# ESP32.net
KiCad netlist of a schematic drawn in Altium Designer
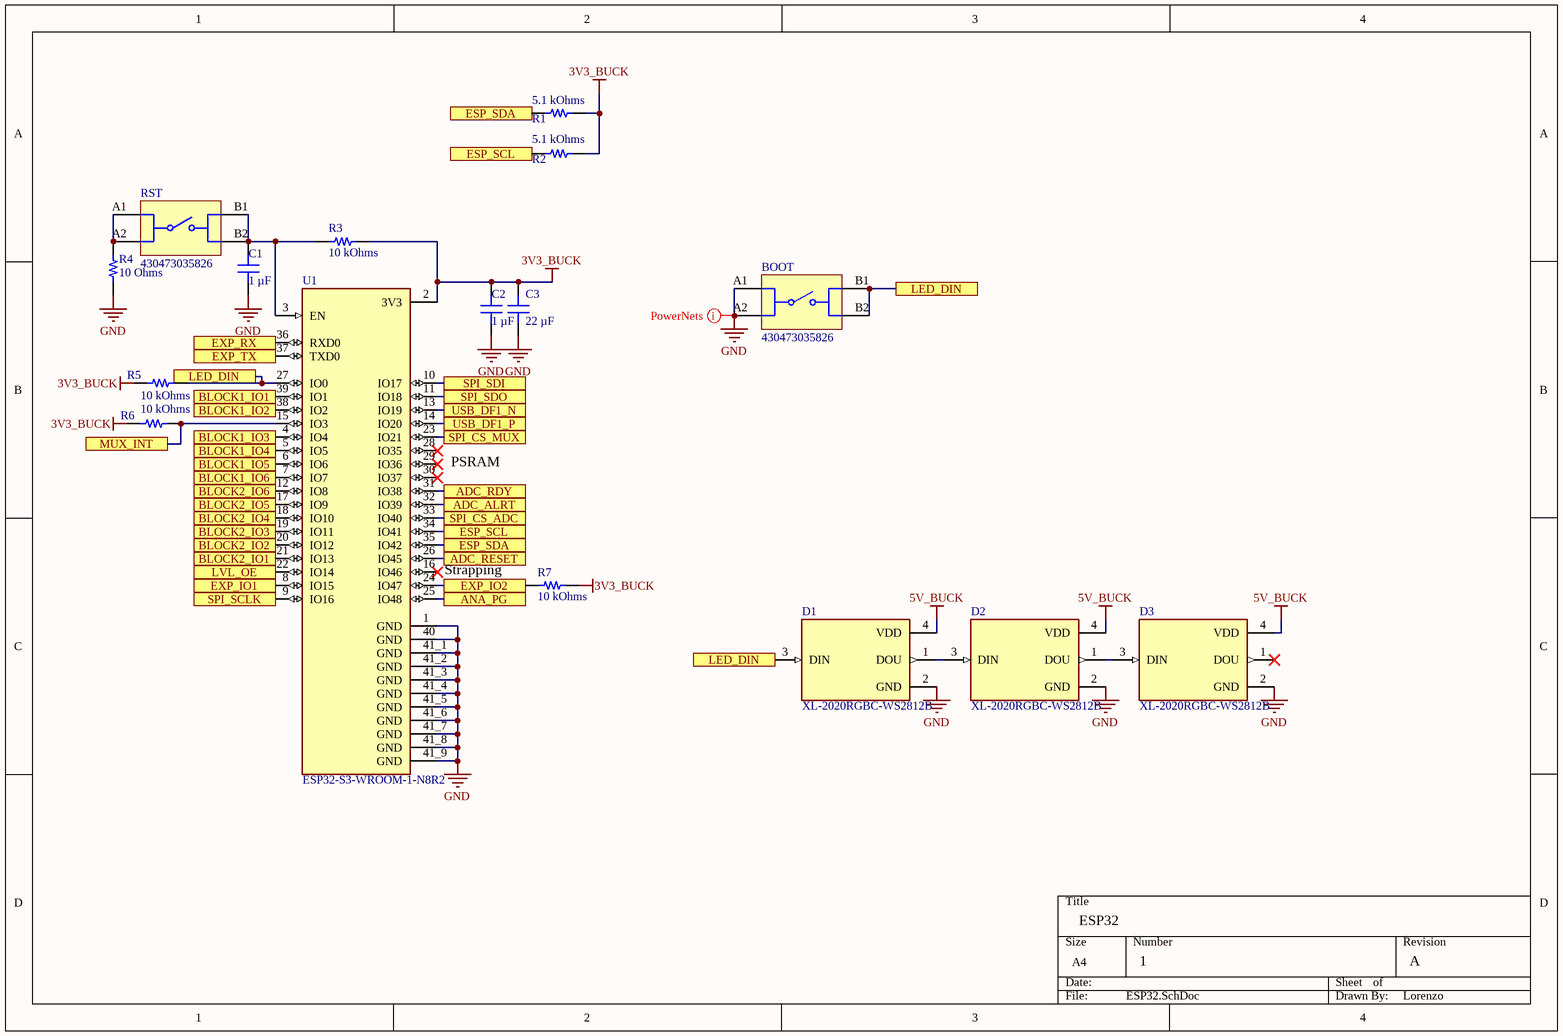
[diagram p0: ESP32.SchDoc]

(export (version "E")
  (design (tool "Eeschema 10.0.6"))
  (components
    (comp (ref "BOOT")
      (value "430473035826")
      (footprint "430473035826")
      (description "Switch Tactile Spst-no 0.05A 12V")
      (libsource (lib "Altium Content Vault") (part "SPST-NO_4P"))
    )
    (comp (ref "C1")
      (value "1 µF")
      (footprint "CAP 0603_1608")
      (description "CAP CER 1UF 50V X5R 0603")
      (fields
        (field (name "PART NUMBER") "C1608X5R1H105K080AB")
        (field (name "MANUFACTURER") "TDK Corporation")
      )
      (libsource (lib "Altium Database Library V2 Local") (part "Capacitor"))
    )
    (comp (ref "C2")
      (value "1 µF")
      (footprint "CAP 0603_1608")
      (description "CAP CER 1UF 50V X5R 0603")
      (fields
        (field (name "PART NUMBER") "C1608X5R1H105K080AB")
        (field (name "MANUFACTURER") "TDK Corporation")
      )
      (libsource (lib "Altium Database Library V2 Local") (part "Capacitor"))
    )
    (comp (ref "C3")
      (value "22 µF")
      (footprint "CAP 0603_1608")
      (description "CAP CER 22UF 6.3V X6S 0603")
      (fields (field (name "PART NUMBER") "CC0603MRX6S5BB226") (field (name "MANUFACTURER") "Yageo"))
      (libsource (lib "Altium Database Library V2 Local") (part "Capacitor"))
    )
    (comp (ref "D1")
      (value "XL-2020RGBC-WS2812B")
      (footprint "LED_XL-2020RGBC-WS2812B")
      (description "2020 RGB LED(BUILT-IN IC)")
      (fields (field (name "MF") "XINGLIGHT"))
      (libsource (lib "Lib") (part "XL-2020RGBC-WS2812B"))
    )
    (comp (ref "D2")
      (value "XL-2020RGBC-WS2812B")
      (footprint "LED_XL-2020RGBC-WS2812B")
      (description "2020 RGB LED(BUILT-IN IC)")
      (fields (field (name "MF") "XINGLIGHT"))
      (libsource (lib "Lib") (part "XL-2020RGBC-WS2812B"))
    )
    (comp (ref "D3")
      (value "XL-2020RGBC-WS2812B")
      (footprint "LED_XL-2020RGBC-WS2812B")
      (description "2020 RGB LED(BUILT-IN IC)")
      (fields (field (name "MF") "XINGLIGHT"))
      (libsource (lib "Lib") (part "XL-2020RGBC-WS2812B"))
    )
    (comp (ref "R1")
      (value "5.1 kOhms")
      (footprint "RES 0603_1608")
      (description "RES 5.1K OHM 1% 1/10W 0603")
      (fields
        (field (name "PART NUMBER") "RMCF0603FT5K10")
        (field (name "MANUFACTURER") "Stackpole Electronics Inc")
      )
      (libsource (lib "Altium Database Library V2 Local") (part "Resistor"))
    )
    (comp (ref "R2")
      (value "5.1 kOhms")
      (footprint "RES 0603_1608")
      (description "RES 5.1K OHM 1% 1/10W 0603")
      (fields
        (field (name "PART NUMBER") "RMCF0603FT5K10")
        (field (name "MANUFACTURER") "Stackpole Electronics Inc")
      )
      (libsource (lib "Altium Database Library V2 Local") (part "Resistor"))
    )
    (comp (ref "R3")
      (value "10 kOhms")
      (footprint "RES 0603_1608")
      (description "RES 10K OHM 1% 1/5W 0603")
      (fields
        (field (name "PART NUMBER") "SG73S1JTTD1002F")
        (field (name "MANUFACTURER") "KOA Speer Electronics, Inc.")
      )
      (libsource (lib "Altium Database Library V2 Local") (part "Resistor"))
    )
    (comp (ref "R4")
      (value "10 Ohms")
      (footprint "RES 0603_1608")
      (description "RES SMD 10 OHM 1% 1/4W 0603")
      (fields (field (name "PART NUMBER") "ESR03EZPF10R0") (field (name "MANUFACTURER") "Rohm Semiconductor"))
      (libsource (lib "Altium Database Library V2 Local") (part "Resistor"))
    )
    (comp (ref "R5")
      (value "10 kOhms")
      (footprint "RES 0603_1608")
      (description "RES 10K OHM 1% 1/5W 0603")
      (fields
        (field (name "PART NUMBER") "SG73S1JTTD1002F")
        (field (name "MANUFACTURER") "KOA Speer Electronics, Inc.")
      )
      (libsource (lib "Altium Database Library V2 Local") (part "Resistor"))
    )
    (comp (ref "R6")
      (value "10 kOhms")
      (footprint "RES 0603_1608")
      (description "RES 10K OHM 1% 1/5W 0603")
      (fields
        (field (name "PART NUMBER") "SG73S1JTTD1002F")
        (field (name "MANUFACTURER") "KOA Speer Electronics, Inc.")
      )
      (libsource (lib "Altium Database Library V2 Local") (part "Resistor"))
    )
    (comp (ref "R7")
      (value "10 kOhms")
      (footprint "RES 0603_1608")
      (description "RES 10K OHM 1% 1/5W 0603")
      (fields
        (field (name "PART NUMBER") "SG73S1JTTD1002F")
        (field (name "MANUFACTURER") "KOA Speer Electronics, Inc.")
      )
      (libsource (lib "Altium Database Library V2 Local") (part "Resistor"))
    )
    (comp (ref "RST")
      (value "430473035826")
      (footprint "430473035826")
      (description "Switch Tactile Spst-no 0.05A 12V")
      (libsource (lib "Altium Content Vault") (part "SPST-NO_4P"))
    )
    (comp (ref "U1")
      (value "ESP32-S3-WROOM-1-N8R2")
      (footprint "XCVR_ESP32-S3-WROOM-1-N8R2")
      (description "WiFi 802.11a/b/g/n, Bluetooth v5.0 Transceiver Module 2.4GHz Antenna Not Included -")
      (fields (field (name "MF") "Espressif Systems"))
      (libsource (lib "Lib") (part "ESP32-S3-WROOM-1-N8R2"))
    )
  )
  (nets
    (net (code "1") (name "/ADC_ALRT") (class "Default")
      (node (ref "U1") (pin "32") (pinfunction "IO39_32") (pintype "bidirectional"))
    )
    (net (code "2") (name "/ADC_RDY") (class "Default")
      (node (ref "U1") (pin "31") (pinfunction "IO38_31") (pintype "bidirectional"))
    )
    (net (code "3") (name "/ADC_RESET") (class "Default")
      (node (ref "U1") (pin "26") (pinfunction "IO45_26") (pintype "bidirectional"))
    )
    (net (code "4") (name "/ANA_PG") (class "Default")
      (node (ref "U1") (pin "25") (pinfunction "IO48_25") (pintype "bidirectional"))
    )
    (net (code "5") (name "/BLOCK1_IO1") (class "Default")
      (node (ref "U1") (pin "39") (pinfunction "IO1_39") (pintype "bidirectional"))
    )
    (net (code "6") (name "/BLOCK1_IO2") (class "Default")
      (node (ref "U1") (pin "38") (pinfunction "IO2_38") (pintype "bidirectional"))
    )
    (net (code "7") (name "/BLOCK1_IO3") (class "Default")
      (node (ref "U1") (pin "4") (pinfunction "IO4_4") (pintype "bidirectional"))
    )
    (net (code "8") (name "/BLOCK1_IO4") (class "Default")
      (node (ref "U1") (pin "5") (pinfunction "IO5_5") (pintype "bidirectional"))
    )
    (net (code "9") (name "/BLOCK1_IO5") (class "Default")
      (node (ref "U1") (pin "6") (pinfunction "IO6_6") (pintype "bidirectional"))
    )
    (net (code "10") (name "/BLOCK1_IO6") (class "Default")
      (node (ref "U1") (pin "7") (pinfunction "IO7_7") (pintype "bidirectional"))
    )
    (net (code "11") (name "/BLOCK2_IO1") (class "Default")
      (node (ref "U1") (pin "21") (pinfunction "IO13_21") (pintype "bidirectional"))
    )
    (net (code "12") (name "/BLOCK2_IO2") (class "Default")
      (node (ref "U1") (pin "20") (pinfunction "IO12_20") (pintype "bidirectional"))
    )
    (net (code "13") (name "/BLOCK2_IO3") (class "Default")
      (node (ref "U1") (pin "19") (pinfunction "IO11_19") (pintype "bidirectional"))
    )
    (net (code "14") (name "/BLOCK2_IO4") (class "Default")
      (node (ref "U1") (pin "18") (pinfunction "IO10_18") (pintype "bidirectional"))
    )
    (net (code "15") (name "/BLOCK2_IO5") (class "Default")
      (node (ref "U1") (pin "17") (pinfunction "IO9_17") (pintype "bidirectional"))
    )
    (net (code "16") (name "/BLOCK2_IO6") (class "Default")
      (node (ref "U1") (pin "12") (pinfunction "IO8_12") (pintype "bidirectional"))
    )
    (net (code "17") (name "/ESP_SCL") (class "Default")
      (node (ref "R2") (pin "1") (pinfunction "1_1") (pintype "passive"))
      (node (ref "U1") (pin "34") (pinfunction "IO41_34") (pintype "bidirectional"))
    )
    (net (code "18") (name "/ESP_SDA") (class "Default")
      (node (ref "R1") (pin "1") (pinfunction "1_1") (pintype "passive"))
      (node (ref "U1") (pin "35") (pinfunction "IO42_35") (pintype "bidirectional"))
    )
    (net (code "19") (name "/EXP_IO1") (class "Default")
      (node (ref "U1") (pin "8") (pinfunction "IO15_8") (pintype "bidirectional"))
    )
    (net (code "20") (name "/EXP_IO2") (class "Default")
      (node (ref "R7") (pin "2") (pinfunction "2_2") (pintype "passive"))
      (node (ref "U1") (pin "24") (pinfunction "IO47_24") (pintype "bidirectional"))
    )
    (net (code "21") (name "/EXP_RX") (class "Default")
      (node (ref "U1") (pin "36") (pinfunction "RXD0_36") (pintype "bidirectional"))
    )
    (net (code "22") (name "/EXP_TX") (class "Default")
      (node (ref "U1") (pin "37") (pinfunction "TXD0_37") (pintype "bidirectional"))
    )
    (net (code "23") (name "/LED_DIN") (class "Default")
      (node (ref "BOOT") (pin "B1") (pinfunction "B1_B1") (pintype "passive"))
      (node (ref "BOOT") (pin "B2") (pinfunction "B2_B2") (pintype "passive"))
      (node (ref "D1") (pin "3") (pinfunction "DIN_3") (pintype "input"))
      (node (ref "R5") (pin "2") (pinfunction "2_2") (pintype "passive"))
      (node (ref "U1") (pin "27") (pinfunction "IO0_27") (pintype "bidirectional"))
    )
    (net (code "24") (name "/LVL_OE") (class "Default")
      (node (ref "U1") (pin "22") (pinfunction "IO14_22") (pintype "bidirectional"))
    )
    (net (code "25") (name "/MUX_INT") (class "Default")
      (node (ref "R6") (pin "2") (pinfunction "2_2") (pintype "passive"))
      (node (ref "U1") (pin "15") (pinfunction "IO3_15") (pintype "bidirectional"))
    )
    (net (code "26") (name "/SPI_CS_ADC") (class "Default")
      (node (ref "U1") (pin "33") (pinfunction "IO40_33") (pintype "bidirectional"))
    )
    (net (code "27") (name "/SPI_CS_MUX") (class "Default")
      (node (ref "U1") (pin "23") (pinfunction "IO21_23") (pintype "bidirectional"))
    )
    (net (code "28") (name "/SPI_SCLK") (class "Default")
      (node (ref "U1") (pin "9") (pinfunction "IO16_9") (pintype "bidirectional"))
    )
    (net (code "29") (name "/SPI_SDI") (class "Default")
      (node (ref "U1") (pin "10") (pinfunction "IO17_10") (pintype "bidirectional"))
    )
    (net (code "30") (name "/SPI_SDO") (class "Default")
      (node (ref "U1") (pin "11") (pinfunction "IO18_11") (pintype "bidirectional"))
    )
    (net (code "31") (name "/USB_DF1_N") (class "Default")
      (node (ref "U1") (pin "13") (pinfunction "IO19_13") (pintype "bidirectional"))
    )
    (net (code "32") (name "/USB_DF1_P") (class "Default")
      (node (ref "U1") (pin "14") (pinfunction "IO20_14") (pintype "bidirectional"))
    )
    (net (code "33") (name "3V3_BUCK") (class "Default")
      (node (ref "C2") (pin "2") (pinfunction "2_2") (pintype "passive"))
      (node (ref "C3") (pin "2") (pinfunction "2_2") (pintype "passive"))
      (node (ref "R1") (pin "2") (pinfunction "2_2") (pintype "passive"))
      (node (ref "R2") (pin "2") (pinfunction "2_2") (pintype "passive"))
      (node (ref "R3") (pin "2") (pinfunction "2_2") (pintype "passive"))
      (node (ref "R5") (pin "1") (pinfunction "1_1") (pintype "passive"))
      (node (ref "R6") (pin "1") (pinfunction "1_1") (pintype "passive"))
      (node (ref "R7") (pin "1") (pinfunction "1_1") (pintype "passive"))
      (node (ref "U1") (pin "2") (pinfunction "3V3_2") (pintype "power_in"))
    )
    (net (code "34") (name "5V_BUCK") (class "Default")
      (node (ref "D1") (pin "4") (pinfunction "VDD_4") (pintype "power_in"))
      (node (ref "D2") (pin "4") (pinfunction "VDD_4") (pintype "power_in"))
      (node (ref "D3") (pin "4") (pinfunction "VDD_4") (pintype "power_in"))
    )
    (net (code "35") (name "GND") (class "Default")
      (node (ref "BOOT") (pin "A1") (pinfunction "A1_A1") (pintype "passive"))
      (node (ref "BOOT") (pin "A2") (pinfunction "A2_A2") (pintype "passive"))
      (node (ref "C1") (pin "1") (pinfunction "1_1") (pintype "passive"))
      (node (ref "C2") (pin "1") (pinfunction "1_1") (pintype "passive"))
      (node (ref "C3") (pin "1") (pinfunction "1_1") (pintype "passive"))
      (node (ref "D1") (pin "2") (pinfunction "GND_2") (pintype "power_in"))
      (node (ref "D2") (pin "2") (pinfunction "GND_2") (pintype "power_in"))
      (node (ref "D3") (pin "2") (pinfunction "GND_2") (pintype "power_in"))
      (node (ref "R4") (pin "1") (pinfunction "1_1") (pintype "passive"))
      (node (ref "U1") (pin "1") (pinfunction "GND_1") (pintype "power_in"))
      (node (ref "U1") (pin "40") (pinfunction "GND_40") (pintype "power_in"))
      (node (ref "U1") (pin "41_1") (pinfunction "GND_41_1") (pintype "power_in"))
      (node (ref "U1") (pin "41_2") (pinfunction "GND_41_2") (pintype "power_in"))
      (node (ref "U1") (pin "41_3") (pinfunction "GND_41_3") (pintype "power_in"))
      (node (ref "U1") (pin "41_4") (pinfunction "GND_41_4") (pintype "power_in"))
      (node (ref "U1") (pin "41_5") (pinfunction "GND_41_5") (pintype "power_in"))
      (node (ref "U1") (pin "41_6") (pinfunction "GND_41_6") (pintype "power_in"))
      (node (ref "U1") (pin "41_7") (pinfunction "GND_41_7") (pintype "power_in"))
      (node (ref "U1") (pin "41_8") (pinfunction "GND_41_8") (pintype "power_in"))
      (node (ref "U1") (pin "41_9") (pinfunction "GND_41_9") (pintype "power_in"))
    )
    (net (code "36") (name "Net-(D1-DOU)") (class "Default")
      (node (ref "D1") (pin "1") (pinfunction "DOU_1") (pintype "output"))
      (node (ref "D2") (pin "3") (pinfunction "DIN_3") (pintype "input"))
    )
    (net (code "37") (name "Net-(D2-DOU)") (class "Default")
      (node (ref "D2") (pin "1") (pinfunction "DOU_1") (pintype "output"))
      (node (ref "D3") (pin "3") (pinfunction "DIN_3") (pintype "input"))
    )
    (net (code "38") (name "Net-(R4-Pad2)") (class "Default")
      (node (ref "R4") (pin "2") (pinfunction "2_2") (pintype "passive"))
      (node (ref "RST") (pin "A1") (pinfunction "A1_A1") (pintype "passive"))
      (node (ref "RST") (pin "A2") (pinfunction "A2_A2") (pintype "passive"))
    )
    (net (code "39") (name "Net-(U1-EN)") (class "Default")
      (node (ref "C1") (pin "2") (pinfunction "2_2") (pintype "passive"))
      (node (ref "R3") (pin "1") (pinfunction "1_1") (pintype "passive"))
      (node (ref "RST") (pin "B1") (pinfunction "B1_B1") (pintype "passive"))
      (node (ref "RST") (pin "B2") (pinfunction "B2_B2") (pintype "passive"))
      (node (ref "U1") (pin "3") (pinfunction "EN_3") (pintype "input"))
    )
    (net (code "40") (name "unconnected-(D3-DOU-Pad1)") (class "Default")
      (node (ref "D3") (pin "1") (pinfunction "DOU_1") (pintype "output+no_connect"))
    )
    (net (code "41") (name "unconnected-(U1-IO35-Pad28)") (class "Default")
      (node (ref "U1") (pin "28") (pinfunction "IO35_28") (pintype "bidirectional+no_connect"))
    )
    (net (code "42") (name "unconnected-(U1-IO36-Pad29)") (class "Default")
      (node (ref "U1") (pin "29") (pinfunction "IO36_29") (pintype "bidirectional+no_connect"))
    )
    (net (code "43") (name "unconnected-(U1-IO37-Pad30)") (class "Default")
      (node (ref "U1") (pin "30") (pinfunction "IO37_30") (pintype "bidirectional+no_connect"))
    )
    (net (code "44") (name "unconnected-(U1-IO46-Pad16)") (class "Default")
      (node (ref "U1") (pin "16") (pinfunction "IO46_16") (pintype "bidirectional+no_connect"))
    )
  )
)
